# CD74HC4067_MUX.net
KiCad netlist of a schematic drawn in Altium Designer
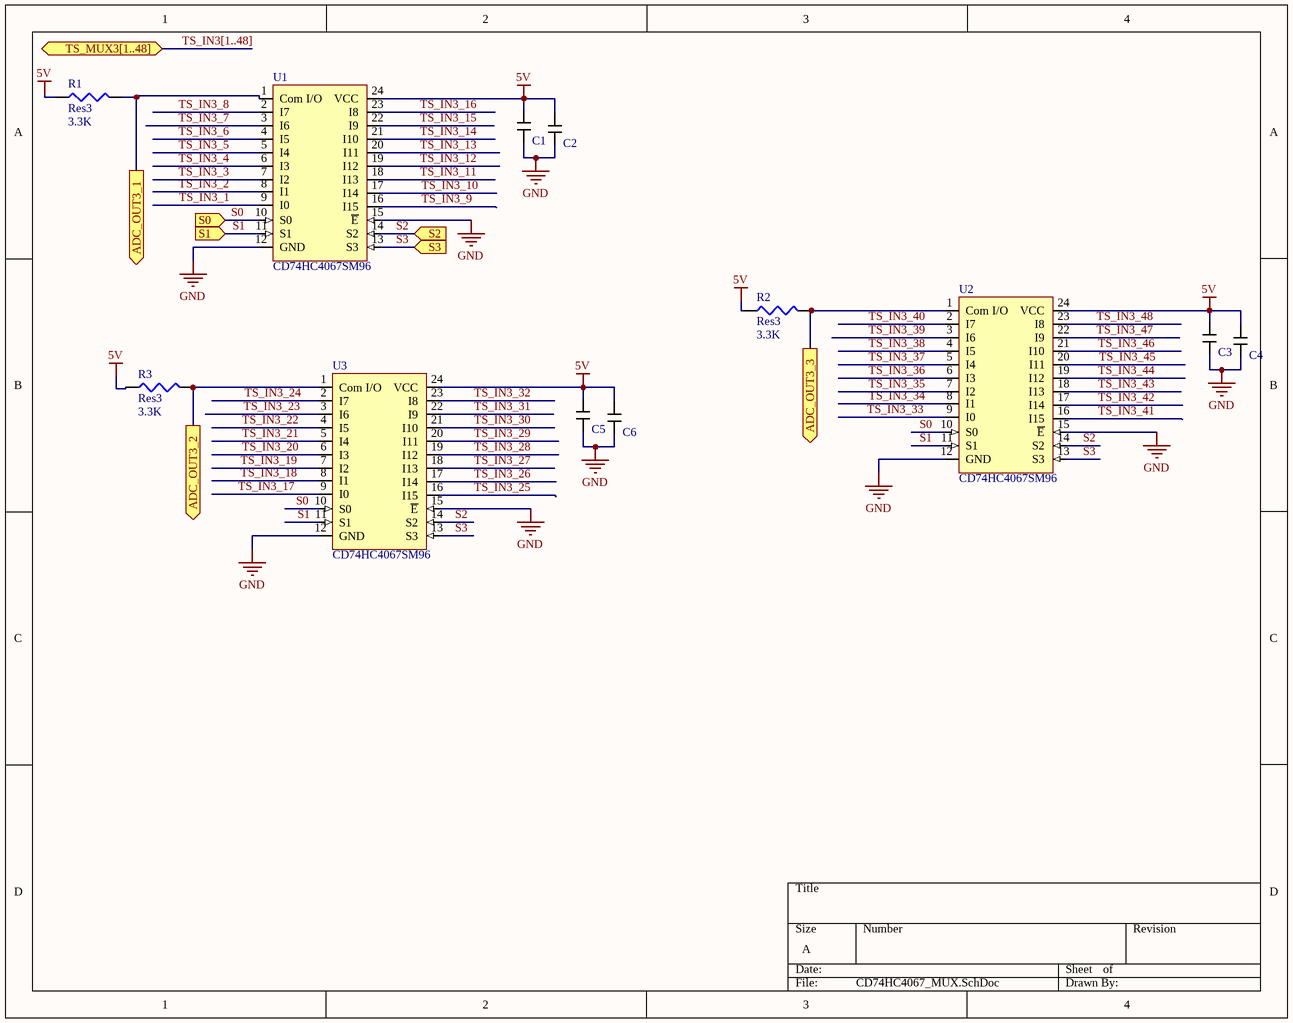
[diagram p0: CD74HC4067_MUX.SchDoc]

(export (version "E")
  (design (tool "Eeschema 10.0.6"))
  (components
    (comp (ref "C1")
      (value "0.1uF Cap")
      (footprint "CAPC1608X09M")
      (description "C0603C101K8GAC7867 Kemet Capacitor")
      (libsource (lib "0.1_uF_Kemet_Cap") (part "0.1uF Cap"))
    )
    (comp (ref "C2")
      (value "1uF Samsung Cap")
      (footprint "CAPC1608X09M")
      (libsource (lib "1uF_Samsung_Cap") (part "1uF Samsung Cap"))
    )
    (comp (ref "C3")
      (value "0.1uF Cap")
      (footprint "CAPC1608X09M")
      (description "C0603C101K8GAC7867 Kemet Capacitor")
      (libsource (lib "0.1_uF_Kemet_Cap") (part "0.1uF Cap"))
    )
    (comp (ref "C4")
      (value "1uF Samsung Cap")
      (footprint "CAPC1608X09M")
      (libsource (lib "1uF_Samsung_Cap") (part "1uF Samsung Cap"))
    )
    (comp (ref "C5")
      (value "0.1uF Cap")
      (footprint "CAPC1608X09M")
      (description "C0603C101K8GAC7867 Kemet Capacitor")
      (libsource (lib "0.1_uF_Kemet_Cap") (part "0.1uF Cap"))
    )
    (comp (ref "C6")
      (value "1uF Samsung Cap")
      (footprint "CAPC1608X09M")
      (libsource (lib "1uF_Samsung_Cap") (part "1uF Samsung Cap"))
    )
    (comp (ref "R1")
      (value "Res3")
      (footprint "J1-0603")
      (description "Resistor")
      (fields (field (name "ALTIUM_VALUE") "3.3K") (field (name "PUBLISHER") "Altium Limited"))
      (libsource (lib "Miscellaneous Devices") (part "Res3"))
    )
    (comp (ref "R2")
      (value "Res3")
      (footprint "J1-0603")
      (description "Resistor")
      (fields (field (name "ALTIUM_VALUE") "3.3K") (field (name "PUBLISHER") "Altium Limited"))
      (libsource (lib "Miscellaneous Devices") (part "Res3"))
    )
    (comp (ref "R3")
      (value "Res3")
      (footprint "J1-0603")
      (description "Resistor")
      (fields (field (name "ALTIUM_VALUE") "3.3K") (field (name "PUBLISHER") "Altium Limited"))
      (libsource (lib "Miscellaneous Devices") (part "Res3"))
    )
    (comp (ref "U1")
      (value "CD74HC4067SM96")
      (footprint "SOIC-24_MUX")
      (libsource (lib "TI_Mux") (part "CD74HC4067SM96"))
    )
    (comp (ref "U2")
      (value "CD74HC4067SM96")
      (footprint "SOIC-24_MUX")
      (libsource (lib "TI_Mux") (part "CD74HC4067SM96"))
    )
    (comp (ref "U3")
      (value "CD74HC4067SM96")
      (footprint "SOIC-24_MUX")
      (libsource (lib "TI_Mux") (part "CD74HC4067SM96"))
    )
  )
  (nets
    (net (code "49") (name "/ADC_OUT3_1") (class "Default")
      (node (ref "R1") (pin "2") (pinfunction "2_2") (pintype "passive"))
      (node (ref "U1") (pin "1") (pinfunction "Com_I/O_1") (pintype "bidirectional"))
    )
    (net (code "50") (name "/ADC_OUT3_2") (class "Default")
      (node (ref "R3") (pin "2") (pinfunction "2_2") (pintype "passive"))
      (node (ref "U3") (pin "1") (pinfunction "Com_I/O_1") (pintype "bidirectional"))
    )
    (net (code "51") (name "/ADC_OUT3_3") (class "Default")
      (node (ref "R2") (pin "2") (pinfunction "2_2") (pintype "passive"))
      (node (ref "U2") (pin "1") (pinfunction "Com_I/O_1") (pintype "bidirectional"))
    )
    (net (code "52") (name "/S0") (class "Default")
      (node (ref "U1") (pin "10") (pinfunction "S0_10") (pintype "input"))
      (node (ref "U2") (pin "10") (pinfunction "S0_10") (pintype "input"))
      (node (ref "U3") (pin "10") (pinfunction "S0_10") (pintype "input"))
    )
    (net (code "53") (name "/S1") (class "Default")
      (node (ref "U1") (pin "11") (pinfunction "S1_11") (pintype "input"))
      (node (ref "U2") (pin "11") (pinfunction "S1_11") (pintype "input"))
      (node (ref "U3") (pin "11") (pinfunction "S1_11") (pintype "input"))
    )
    (net (code "54") (name "/S2") (class "Default")
      (node (ref "U1") (pin "14") (pinfunction "S2_14") (pintype "input"))
      (node (ref "U2") (pin "14") (pinfunction "S2_14") (pintype "input"))
      (node (ref "U3") (pin "14") (pinfunction "S2_14") (pintype "input"))
    )
    (net (code "55") (name "/S3") (class "Default")
      (node (ref "U1") (pin "13") (pinfunction "S3_13") (pintype "input"))
      (node (ref "U2") (pin "13") (pinfunction "S3_13") (pintype "input"))
      (node (ref "U3") (pin "13") (pinfunction "S3_13") (pintype "input"))
    )
    (net (code "57") (name "/TS_IN3_1") (class "Default")
      (node (ref "U1") (pin "9") (pinfunction "I0_9") (pintype "passive"))
    )
    (net (code "58") (name "/TS_IN3_2") (class "Default")
      (node (ref "U1") (pin "8") (pinfunction "I1_8") (pintype "passive"))
    )
    (net (code "59") (name "/TS_IN3_3") (class "Default")
      (node (ref "U1") (pin "7") (pinfunction "I2_7") (pintype "passive"))
    )
    (net (code "60") (name "/TS_IN3_4") (class "Default")
      (node (ref "U1") (pin "6") (pinfunction "I3_6") (pintype "passive"))
    )
    (net (code "61") (name "/TS_IN3_5") (class "Default")
      (node (ref "U1") (pin "5") (pinfunction "I4_5") (pintype "passive"))
    )
    (net (code "62") (name "/TS_IN3_6") (class "Default")
      (node (ref "U1") (pin "4") (pinfunction "I5_4") (pintype "passive"))
    )
    (net (code "63") (name "/TS_IN3_7") (class "Default")
      (node (ref "U1") (pin "3") (pinfunction "I6_3") (pintype "passive"))
    )
    (net (code "64") (name "/TS_IN3_8") (class "Default")
      (node (ref "U1") (pin "2") (pinfunction "I7_2") (pintype "passive"))
    )
    (net (code "65") (name "/TS_IN3_9") (class "Default")
      (node (ref "U1") (pin "16") (pinfunction "I15_16") (pintype "passive"))
    )
    (net (code "66") (name "/TS_IN3_10") (class "Default")
      (node (ref "U1") (pin "17") (pinfunction "I14_17") (pintype "passive"))
    )
    (net (code "67") (name "/TS_IN3_11") (class "Default")
      (node (ref "U1") (pin "18") (pinfunction "I13_18") (pintype "passive"))
    )
    (net (code "68") (name "/TS_IN3_12") (class "Default")
      (node (ref "U1") (pin "19") (pinfunction "I12_19") (pintype "passive"))
    )
    (net (code "69") (name "/TS_IN3_13") (class "Default")
      (node (ref "U1") (pin "20") (pinfunction "I11_20") (pintype "passive"))
    )
    (net (code "70") (name "/TS_IN3_14") (class "Default")
      (node (ref "U1") (pin "21") (pinfunction "I10_21") (pintype "passive"))
    )
    (net (code "71") (name "/TS_IN3_15") (class "Default")
      (node (ref "U1") (pin "22") (pinfunction "I9_22") (pintype "passive"))
    )
    (net (code "72") (name "/TS_IN3_16") (class "Default")
      (node (ref "U1") (pin "23") (pinfunction "I8_23") (pintype "passive"))
    )
    (net (code "73") (name "/TS_IN3_17") (class "Default")
      (node (ref "U3") (pin "9") (pinfunction "I0_9") (pintype "passive"))
    )
    (net (code "74") (name "/TS_IN3_18") (class "Default")
      (node (ref "U3") (pin "8") (pinfunction "I1_8") (pintype "passive"))
    )
    (net (code "75") (name "/TS_IN3_19") (class "Default")
      (node (ref "U3") (pin "7") (pinfunction "I2_7") (pintype "passive"))
    )
    (net (code "76") (name "/TS_IN3_20") (class "Default")
      (node (ref "U3") (pin "6") (pinfunction "I3_6") (pintype "passive"))
    )
    (net (code "77") (name "/TS_IN3_21") (class "Default")
      (node (ref "U3") (pin "5") (pinfunction "I4_5") (pintype "passive"))
    )
    (net (code "78") (name "/TS_IN3_22") (class "Default")
      (node (ref "U3") (pin "4") (pinfunction "I5_4") (pintype "passive"))
    )
    (net (code "79") (name "/TS_IN3_23") (class "Default")
      (node (ref "U3") (pin "3") (pinfunction "I6_3") (pintype "passive"))
    )
    (net (code "80") (name "/TS_IN3_24") (class "Default")
      (node (ref "U3") (pin "2") (pinfunction "I7_2") (pintype "passive"))
    )
    (net (code "81") (name "/TS_IN3_25") (class "Default")
      (node (ref "U3") (pin "16") (pinfunction "I15_16") (pintype "passive"))
    )
    (net (code "82") (name "/TS_IN3_26") (class "Default")
      (node (ref "U3") (pin "17") (pinfunction "I14_17") (pintype "passive"))
    )
    (net (code "83") (name "/TS_IN3_27") (class "Default")
      (node (ref "U3") (pin "18") (pinfunction "I13_18") (pintype "passive"))
    )
    (net (code "84") (name "/TS_IN3_28") (class "Default")
      (node (ref "U3") (pin "19") (pinfunction "I12_19") (pintype "passive"))
    )
    (net (code "85") (name "/TS_IN3_29") (class "Default")
      (node (ref "U3") (pin "20") (pinfunction "I11_20") (pintype "passive"))
    )
    (net (code "86") (name "/TS_IN3_30") (class "Default")
      (node (ref "U3") (pin "21") (pinfunction "I10_21") (pintype "passive"))
    )
    (net (code "87") (name "/TS_IN3_31") (class "Default")
      (node (ref "U3") (pin "22") (pinfunction "I9_22") (pintype "passive"))
    )
    (net (code "88") (name "/TS_IN3_32") (class "Default")
      (node (ref "U3") (pin "23") (pinfunction "I8_23") (pintype "passive"))
    )
    (net (code "89") (name "/TS_IN3_33") (class "Default")
      (node (ref "U2") (pin "9") (pinfunction "I0_9") (pintype "passive"))
    )
    (net (code "90") (name "/TS_IN3_34") (class "Default")
      (node (ref "U2") (pin "8") (pinfunction "I1_8") (pintype "passive"))
    )
    (net (code "91") (name "/TS_IN3_35") (class "Default")
      (node (ref "U2") (pin "7") (pinfunction "I2_7") (pintype "passive"))
    )
    (net (code "92") (name "/TS_IN3_36") (class "Default")
      (node (ref "U2") (pin "6") (pinfunction "I3_6") (pintype "passive"))
    )
    (net (code "93") (name "/TS_IN3_37") (class "Default")
      (node (ref "U2") (pin "5") (pinfunction "I4_5") (pintype "passive"))
    )
    (net (code "94") (name "/TS_IN3_38") (class "Default")
      (node (ref "U2") (pin "4") (pinfunction "I5_4") (pintype "passive"))
    )
    (net (code "95") (name "/TS_IN3_39") (class "Default")
      (node (ref "U2") (pin "3") (pinfunction "I6_3") (pintype "passive"))
    )
    (net (code "96") (name "/TS_IN3_40") (class "Default")
      (node (ref "U2") (pin "2") (pinfunction "I7_2") (pintype "passive"))
    )
    (net (code "97") (name "/TS_IN3_41") (class "Default")
      (node (ref "U2") (pin "16") (pinfunction "I15_16") (pintype "passive"))
    )
    (net (code "98") (name "/TS_IN3_42") (class "Default")
      (node (ref "U2") (pin "17") (pinfunction "I14_17") (pintype "passive"))
    )
    (net (code "99") (name "/TS_IN3_43") (class "Default")
      (node (ref "U2") (pin "18") (pinfunction "I13_18") (pintype "passive"))
    )
    (net (code "100") (name "/TS_IN3_44") (class "Default")
      (node (ref "U2") (pin "19") (pinfunction "I12_19") (pintype "passive"))
    )
    (net (code "101") (name "/TS_IN3_45") (class "Default")
      (node (ref "U2") (pin "20") (pinfunction "I11_20") (pintype "passive"))
    )
    (net (code "102") (name "/TS_IN3_46") (class "Default")
      (node (ref "U2") (pin "21") (pinfunction "I10_21") (pintype "passive"))
    )
    (net (code "103") (name "/TS_IN3_47") (class "Default")
      (node (ref "U2") (pin "22") (pinfunction "I9_22") (pintype "passive"))
    )
    (net (code "104") (name "/TS_IN3_48") (class "Default")
      (node (ref "U2") (pin "23") (pinfunction "I8_23") (pintype "passive"))
    )
    (net (code "105") (name "5V") (class "Default")
      (node (ref "C1") (pin "2") (pinfunction "2_2") (pintype "passive"))
      (node (ref "C2") (pin "2") (pinfunction "2_2") (pintype "passive"))
      (node (ref "C3") (pin "2") (pinfunction "2_2") (pintype "passive"))
      (node (ref "C4") (pin "2") (pinfunction "2_2") (pintype "passive"))
      (node (ref "C5") (pin "2") (pinfunction "2_2") (pintype "passive"))
      (node (ref "C6") (pin "2") (pinfunction "2_2") (pintype "passive"))
      (node (ref "R1") (pin "1") (pinfunction "1_1") (pintype "passive"))
      (node (ref "R2") (pin "1") (pinfunction "1_1") (pintype "passive"))
      (node (ref "R3") (pin "1") (pinfunction "1_1") (pintype "passive"))
      (node (ref "U1") (pin "24") (pinfunction "VCC_24") (pintype "power_in"))
      (node (ref "U2") (pin "24") (pinfunction "VCC_24") (pintype "power_in"))
      (node (ref "U3") (pin "24") (pinfunction "VCC_24") (pintype "power_in"))
    )
    (net (code "106") (name "GND") (class "Default")
      (node (ref "C1") (pin "1") (pinfunction "1_1") (pintype "passive"))
      (node (ref "C2") (pin "1") (pinfunction "1_1") (pintype "passive"))
      (node (ref "C3") (pin "1") (pinfunction "1_1") (pintype "passive"))
      (node (ref "C4") (pin "1") (pinfunction "1_1") (pintype "passive"))
      (node (ref "C5") (pin "1") (pinfunction "1_1") (pintype "passive"))
      (node (ref "C6") (pin "1") (pinfunction "1_1") (pintype "passive"))
      (node (ref "U1") (pin "12") (pinfunction "GND_12") (pintype "power_in"))
      (node (ref "U1") (pin "15") (pinfunction "~{E}_15") (pintype "input"))
      (node (ref "U2") (pin "12") (pinfunction "GND_12") (pintype "power_in"))
      (node (ref "U2") (pin "15") (pinfunction "~{E}_15") (pintype "input"))
      (node (ref "U3") (pin "12") (pinfunction "GND_12") (pintype "power_in"))
      (node (ref "U3") (pin "15") (pinfunction "~{E}_15") (pintype "input"))
    )
  )
)
